# spindle_pwm_controller_v1.net
KiCad netlist of a schematic drawn in EAGLE
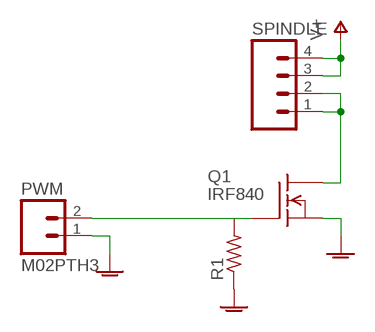
[diagram p0: schematic, sheet 1]

(export (version "E")
  (design (tool "Eeschema 10.0.6"))
  (components
    (comp (ref "PWM")
      (value "M02PTH3")
      (footprint "eagle-import:1X02_LONGPADS")
      (libsource (lib "eagle-import") (part "M02PTH3"))
    )
    (comp (ref "Q1")
      (value "IRF840")
      (footprint "eagle-import:TO220")
      (libsource (lib "eagle-import") (part "IRF840"))
    )
    (comp (ref "R1")
      (value "R-US_0207/7")
      (footprint "eagle-import:0207_7")
      (libsource (lib "eagle-import") (part "R-US_0207/7"))
    )
    (comp (ref "SPINDLE")
      (value "M04LONGPADS")
      (footprint "eagle-import:1X04_LONGPADS")
      (libsource (lib "eagle-import") (part "M04LONGPADS"))
    )
  )
  (nets
    (net (code "1") (name "GNDA") (class "Default")
      (node (ref "PWM") (pin "1") (pinfunction "1_1") (pintype "passive"))
      (node (ref "Q1") (pin "3") (pinfunction "S_3") (pintype "passive"))
      (node (ref "R1") (pin "1") (pinfunction "1_1") (pintype "passive"))
    )
    (net (code "2") (name "Net-(Q1-D)") (class "Default")
      (node (ref "Q1") (pin "2") (pinfunction "D_2") (pintype "passive"))
      (node (ref "SPINDLE") (pin "1") (pinfunction "1_1") (pintype "passive"))
      (node (ref "SPINDLE") (pin "2") (pinfunction "2_2") (pintype "passive"))
    )
    (net (code "3") (name "Net-(Q1-G)") (class "Default")
      (node (ref "PWM") (pin "2") (pinfunction "2_2") (pintype "passive"))
      (node (ref "Q1") (pin "1") (pinfunction "G_1") (pintype "passive"))
      (node (ref "R1") (pin "2") (pinfunction "2_2") (pintype "passive"))
    )
    (net (code "4") (name "V+") (class "Default")
      (node (ref "SPINDLE") (pin "3") (pinfunction "3_3") (pintype "passive"))
      (node (ref "SPINDLE") (pin "4") (pinfunction "4_4") (pintype "passive"))
    )
  )
)
